# main-stm32.net
KiCad netlist of a schematic drawn in EAGLE
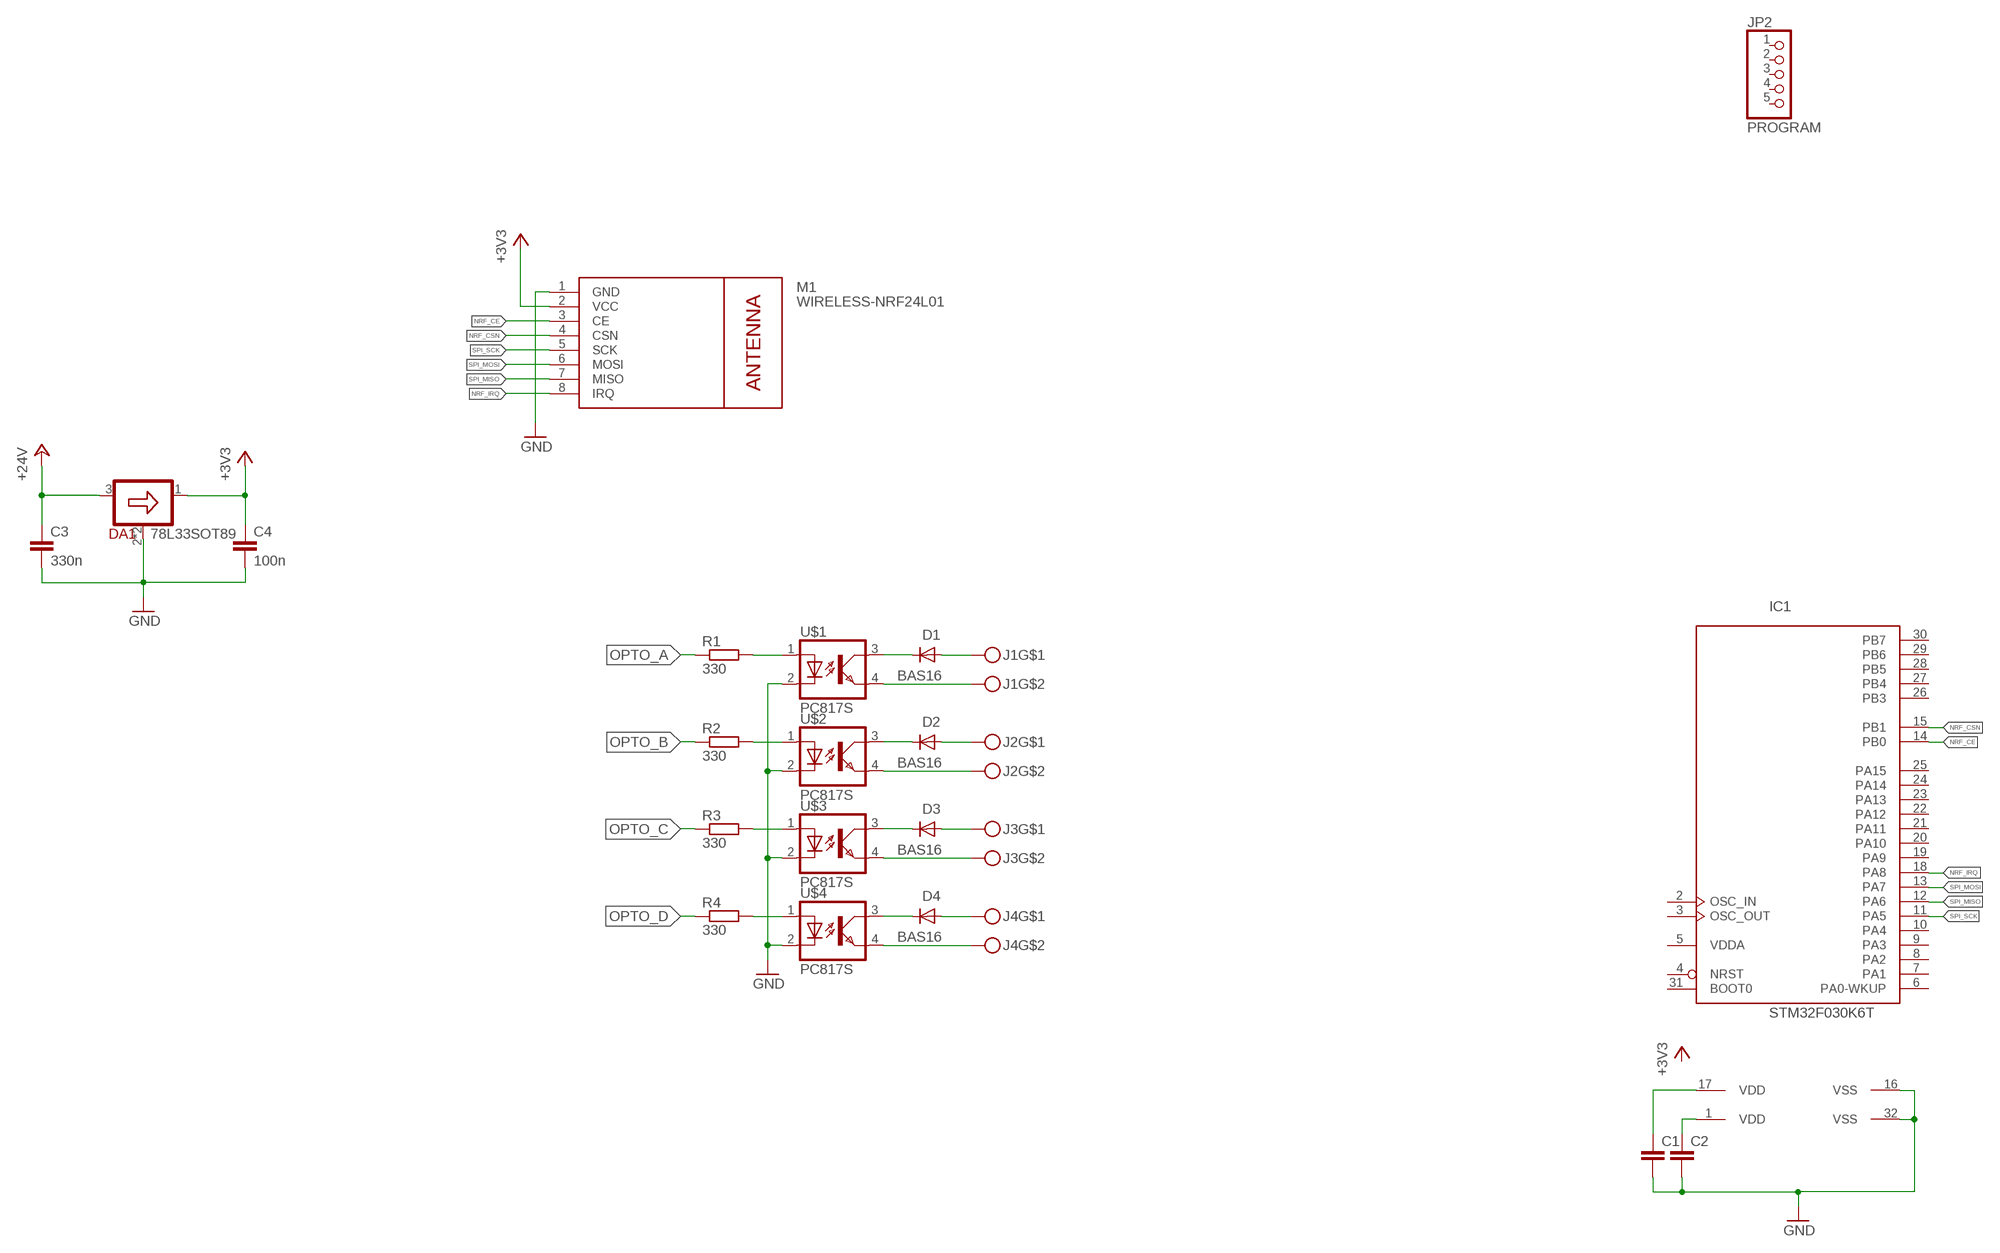
[diagram p0: schematic, sheet 1]

(export (version "E")
  (design (tool "Eeschema 10.0.6"))
  (components
    (comp (ref "C1")
      (value "C-EUC1206")
      (footprint "eagle-import:C1206")
      (libsource (lib "eagle-import") (part "C-EUC1206"))
    )
    (comp (ref "C2")
      (value "C-EUC1206")
      (footprint "eagle-import:C1206")
      (libsource (lib "eagle-import") (part "C-EUC1206"))
    )
    (comp (ref "C3")
      (value "330n")
      (footprint "eagle-import:C1206")
      (libsource (lib "eagle-import") (part "C-EUC1206"))
    )
    (comp (ref "C4")
      (value "100n")
      (footprint "eagle-import:C1206")
      (libsource (lib "eagle-import") (part "C-EUC1206"))
    )
    (comp (ref "D1")
      (value "BAS16")
      (footprint "eagle-import:SOT23")
      (libsource (lib "eagle-import") (part "BAS16"))
    )
    (comp (ref "D2")
      (value "BAS16")
      (footprint "eagle-import:SOT23")
      (libsource (lib "eagle-import") (part "BAS16"))
    )
    (comp (ref "D3")
      (value "BAS16")
      (footprint "eagle-import:SOT23")
      (libsource (lib "eagle-import") (part "BAS16"))
    )
    (comp (ref "D4")
      (value "BAS16")
      (footprint "eagle-import:SOT23")
      (libsource (lib "eagle-import") (part "BAS16"))
    )
    (comp (ref "DA1")
      (value "78L33SOT89")
      (footprint "eagle-import:SOT89")
      (libsource (lib "eagle-import") (part "78L33SOT89"))
    )
    (comp (ref "IC1")
      (value "STM32F030K6T")
      (footprint "eagle-import:LQFP32")
      (libsource (lib "eagle-import") (part "STM32F030KT6"))
    )
    (comp (ref "J1")
      (value "SCREW-TERMINAL-2PIN")
      (footprint "eagle-import:PITCH4.3-PIN2")
      (libsource (lib "eagle-import") (part "SCREW-TERMINAL-2PIN"))
    )
    (comp (ref "J2")
      (value "SCREW-TERMINAL-2PIN")
      (footprint "eagle-import:PITCH4.3-PIN2")
      (libsource (lib "eagle-import") (part "SCREW-TERMINAL-2PIN"))
    )
    (comp (ref "J3")
      (value "SCREW-TERMINAL-2PIN")
      (footprint "eagle-import:PITCH4.3-PIN2")
      (libsource (lib "eagle-import") (part "SCREW-TERMINAL-2PIN"))
    )
    (comp (ref "J4")
      (value "SCREW-TERMINAL-2PIN")
      (footprint "eagle-import:PITCH4.3-PIN2")
      (libsource (lib "eagle-import") (part "SCREW-TERMINAL-2PIN"))
    )
    (comp (ref "JP2")
      (value "PROGRAM")
      (footprint "eagle-import:1X05")
      (libsource (lib "eagle-import") (part "PINHD-1X5"))
    )
    (comp (ref "M1")
      (value "WIRELESS-NRF24L01")
      (footprint "eagle-import:WIRELESS-NRF24L01")
      (libsource (lib "eagle-import") (part "WIRELESS-NRF24L01"))
    )
    (comp (ref "R1")
      (value "330")
      (footprint "eagle-import:R1206")
      (libsource (lib "eagle-import") (part "R-EU_R1206"))
    )
    (comp (ref "R2")
      (value "330")
      (footprint "eagle-import:R1206")
      (libsource (lib "eagle-import") (part "R-EU_R1206"))
    )
    (comp (ref "R3")
      (value "330")
      (footprint "eagle-import:R1206")
      (libsource (lib "eagle-import") (part "R-EU_R1206"))
    )
    (comp (ref "R4")
      (value "330")
      (footprint "eagle-import:R1206")
      (libsource (lib "eagle-import") (part "R-EU_R1206"))
    )
    (comp (ref "U$1")
      (value "PC817S")
      (footprint "eagle-import:SMD4-7")
      (libsource (lib "eagle-import") (part "PC817S"))
    )
    (comp (ref "U$2")
      (value "PC817S")
      (footprint "eagle-import:SMD4-7")
      (libsource (lib "eagle-import") (part "PC817S"))
    )
    (comp (ref "U$3")
      (value "PC817S")
      (footprint "eagle-import:SMD4-7")
      (libsource (lib "eagle-import") (part "PC817S"))
    )
    (comp (ref "U$4")
      (value "PC817S")
      (footprint "eagle-import:SMD4-7")
      (libsource (lib "eagle-import") (part "PC817S"))
    )
  )
  (nets
    (net (code "1") (name "+3V3") (class "Default")
      (node (ref "C4") (pin "1") (pinfunction "1_1") (pintype "passive"))
      (node (ref "DA1") (pin "1") (pinfunction "OUT_1") (pintype "power_in"))
      (node (ref "M1") (pin "2") (pinfunction "VCC_2") (pintype "power_in"))
    )
    (net (code "2") (name "+24V") (class "Default")
      (node (ref "C3") (pin "1") (pinfunction "1_1") (pintype "passive"))
      (node (ref "DA1") (pin "3") (pinfunction "IN_3") (pintype "power_in"))
    )
    (net (code "3") (name "/VDDA") (class "Default")
      (node (ref "IC1") (pin "5") (pinfunction "VDDA_5") (pintype "power_in"))
    )
    (net (code "4") (name "GND") (class "Default")
      (node (ref "C1") (pin "2") (pinfunction "2_2") (pintype "passive"))
      (node (ref "C2") (pin "2") (pinfunction "2_2") (pintype "passive"))
      (node (ref "C3") (pin "2") (pinfunction "2_2") (pintype "passive"))
      (node (ref "C4") (pin "2") (pinfunction "2_2") (pintype "passive"))
      (node (ref "DA1") (pin "2") (pinfunction "GND_2") (pintype "power_in"))
      (node (ref "DA1") (pin "2@1") (pinfunction "GND_2@1") (pintype "power_in"))
      (node (ref "IC1") (pin "16") (pinfunction "VSS_16") (pintype "power_in"))
      (node (ref "IC1") (pin "32") (pinfunction "VSS_32") (pintype "power_in"))
      (node (ref "M1") (pin "1") (pinfunction "GND_1") (pintype "power_in"))
      (node (ref "U$1") (pin "2") (pinfunction "C_2") (pintype "passive"))
      (node (ref "U$2") (pin "2") (pinfunction "C_2") (pintype "passive"))
      (node (ref "U$3") (pin "2") (pinfunction "C_2") (pintype "passive"))
      (node (ref "U$4") (pin "2") (pinfunction "C_2") (pintype "passive"))
    )
    (net (code "5") (name "NRF_CE") (class "Default")
      (node (ref "IC1") (pin "14") (pinfunction "PB0_14") (pintype "bidirectional"))
      (node (ref "M1") (pin "3") (pinfunction "CE_3") (pintype "bidirectional"))
    )
    (net (code "6") (name "NRF_CSN") (class "Default")
      (node (ref "IC1") (pin "15") (pinfunction "PB1_15") (pintype "bidirectional"))
      (node (ref "M1") (pin "4") (pinfunction "CSN_4") (pintype "bidirectional"))
    )
    (net (code "7") (name "NRF_IRQ") (class "Default")
      (node (ref "IC1") (pin "18") (pinfunction "PA8_18") (pintype "bidirectional"))
      (node (ref "M1") (pin "8") (pinfunction "IRQ_8") (pintype "bidirectional"))
    )
    (net (code "8") (name "Net-(C1-Pad1)") (class "Default")
      (node (ref "C1") (pin "1") (pinfunction "1_1") (pintype "passive"))
      (node (ref "IC1") (pin "17") (pinfunction "VDD_17") (pintype "power_in"))
    )
    (net (code "9") (name "Net-(C2-Pad1)") (class "Default")
      (node (ref "C2") (pin "1") (pinfunction "1_1") (pintype "passive"))
      (node (ref "IC1") (pin "1") (pinfunction "VDD_1") (pintype "power_in"))
    )
    (net (code "10") (name "Net-(D1-A)") (class "Default")
      (node (ref "D1") (pin "1") (pinfunction "A_1") (pintype "passive"))
      (node (ref "J1") (pin "1") (pinfunction "KL_1") (pintype "passive"))
    )
    (net (code "11") (name "Net-(D1-K)") (class "Default")
      (node (ref "D1") (pin "3") (pinfunction "K_3") (pintype "passive"))
      (node (ref "U$1") (pin "3") (pinfunction "COL_3") (pintype "passive"))
    )
    (net (code "12") (name "Net-(D2-A)") (class "Default")
      (node (ref "D2") (pin "1") (pinfunction "A_1") (pintype "passive"))
      (node (ref "J2") (pin "1") (pinfunction "KL_1") (pintype "passive"))
    )
    (net (code "13") (name "Net-(D2-K)") (class "Default")
      (node (ref "D2") (pin "3") (pinfunction "K_3") (pintype "passive"))
      (node (ref "U$2") (pin "3") (pinfunction "COL_3") (pintype "passive"))
    )
    (net (code "14") (name "Net-(D3-A)") (class "Default")
      (node (ref "D3") (pin "1") (pinfunction "A_1") (pintype "passive"))
      (node (ref "J3") (pin "1") (pinfunction "KL_1") (pintype "passive"))
    )
    (net (code "15") (name "Net-(D3-K)") (class "Default")
      (node (ref "D3") (pin "3") (pinfunction "K_3") (pintype "passive"))
      (node (ref "U$3") (pin "3") (pinfunction "COL_3") (pintype "passive"))
    )
    (net (code "16") (name "Net-(D4-A)") (class "Default")
      (node (ref "D4") (pin "1") (pinfunction "A_1") (pintype "passive"))
      (node (ref "J4") (pin "1") (pinfunction "KL_1") (pintype "passive"))
    )
    (net (code "17") (name "Net-(D4-K)") (class "Default")
      (node (ref "D4") (pin "3") (pinfunction "K_3") (pintype "passive"))
      (node (ref "U$4") (pin "3") (pinfunction "COL_3") (pintype "passive"))
    )
    (net (code "18") (name "Net-(J1B-KL)") (class "Default")
      (node (ref "J1") (pin "2") (pinfunction "KL_2") (pintype "passive"))
      (node (ref "U$1") (pin "4") (pinfunction "EMIT_4") (pintype "passive"))
    )
    (net (code "19") (name "Net-(J2B-KL)") (class "Default")
      (node (ref "J2") (pin "2") (pinfunction "KL_2") (pintype "passive"))
      (node (ref "U$2") (pin "4") (pinfunction "EMIT_4") (pintype "passive"))
    )
    (net (code "20") (name "Net-(J3B-KL)") (class "Default")
      (node (ref "J3") (pin "2") (pinfunction "KL_2") (pintype "passive"))
      (node (ref "U$3") (pin "4") (pinfunction "EMIT_4") (pintype "passive"))
    )
    (net (code "21") (name "Net-(J4B-KL)") (class "Default")
      (node (ref "J4") (pin "2") (pinfunction "KL_2") (pintype "passive"))
      (node (ref "U$4") (pin "4") (pinfunction "EMIT_4") (pintype "passive"))
    )
    (net (code "22") (name "Net-(U$1-A)") (class "Default")
      (node (ref "R1") (pin "2") (pinfunction "2_2") (pintype "passive"))
      (node (ref "U$1") (pin "1") (pinfunction "A_1") (pintype "passive"))
    )
    (net (code "23") (name "Net-(U$2-A)") (class "Default")
      (node (ref "R2") (pin "2") (pinfunction "2_2") (pintype "passive"))
      (node (ref "U$2") (pin "1") (pinfunction "A_1") (pintype "passive"))
    )
    (net (code "24") (name "Net-(U$3-A)") (class "Default")
      (node (ref "R3") (pin "2") (pinfunction "2_2") (pintype "passive"))
      (node (ref "U$3") (pin "1") (pinfunction "A_1") (pintype "passive"))
    )
    (net (code "25") (name "Net-(U$4-A)") (class "Default")
      (node (ref "R4") (pin "2") (pinfunction "2_2") (pintype "passive"))
      (node (ref "U$4") (pin "1") (pinfunction "A_1") (pintype "passive"))
    )
    (net (code "26") (name "OPTO_A") (class "Default")
      (node (ref "R1") (pin "1") (pinfunction "1_1") (pintype "passive"))
    )
    (net (code "27") (name "OPTO_B") (class "Default")
      (node (ref "R2") (pin "1") (pinfunction "1_1") (pintype "passive"))
    )
    (net (code "28") (name "OPTO_C") (class "Default")
      (node (ref "R3") (pin "1") (pinfunction "1_1") (pintype "passive"))
    )
    (net (code "29") (name "OPTO_D") (class "Default")
      (node (ref "R4") (pin "1") (pinfunction "1_1") (pintype "passive"))
    )
    (net (code "30") (name "SPI_MISO") (class "Default")
      (node (ref "IC1") (pin "12") (pinfunction "PA6_12") (pintype "bidirectional"))
      (node (ref "M1") (pin "7") (pinfunction "MISO_7") (pintype "bidirectional"))
    )
    (net (code "31") (name "SPI_MOSI") (class "Default")
      (node (ref "IC1") (pin "13") (pinfunction "PA7_13") (pintype "bidirectional"))
      (node (ref "M1") (pin "6") (pinfunction "MOSI_6") (pintype "bidirectional"))
    )
    (net (code "32") (name "SPI_SCK") (class "Default")
      (node (ref "IC1") (pin "11") (pinfunction "PA5_11") (pintype "bidirectional"))
      (node (ref "M1") (pin "5") (pinfunction "SCK_5") (pintype "bidirectional"))
    )
    (net (code "33") (name "unconnected-(IC1A-BOOT0-Pad31)") (class "Default")
      (node (ref "IC1") (pin "31") (pinfunction "BOOT0_31") (pintype "input"))
    )
    (net (code "34") (name "unconnected-(IC1A-NRST-Pad4)") (class "Default")
      (node (ref "IC1") (pin "4") (pinfunction "NRST_4") (pintype "bidirectional"))
    )
    (net (code "35") (name "unconnected-(IC1A-OSC_IN-Pad2)") (class "Default")
      (node (ref "IC1") (pin "2") (pinfunction "OSC_IN_2") (pintype "bidirectional"))
    )
    (net (code "36") (name "unconnected-(IC1A-OSC_OUT-Pad3)") (class "Default")
      (node (ref "IC1") (pin "3") (pinfunction "OSC_OUT_3") (pintype "bidirectional"))
    )
    (net (code "37") (name "unconnected-(IC1A-PA0-WKUP-Pad6)") (class "Default")
      (node (ref "IC1") (pin "6") (pinfunction "PA0-WKUP_6") (pintype "bidirectional"))
    )
    (net (code "38") (name "unconnected-(IC1A-PA1-Pad7)") (class "Default")
      (node (ref "IC1") (pin "7") (pinfunction "PA1_7") (pintype "bidirectional"))
    )
    (net (code "39") (name "unconnected-(IC1A-PA2-Pad8)") (class "Default")
      (node (ref "IC1") (pin "8") (pinfunction "PA2_8") (pintype "bidirectional"))
    )
    (net (code "40") (name "unconnected-(IC1A-PA3-Pad9)") (class "Default")
      (node (ref "IC1") (pin "9") (pinfunction "PA3_9") (pintype "bidirectional"))
    )
    (net (code "41") (name "unconnected-(IC1A-PA4-Pad10)") (class "Default")
      (node (ref "IC1") (pin "10") (pinfunction "PA4_10") (pintype "bidirectional"))
    )
    (net (code "42") (name "unconnected-(IC1A-PA9-Pad19)") (class "Default")
      (node (ref "IC1") (pin "19") (pinfunction "PA9_19") (pintype "bidirectional"))
    )
    (net (code "43") (name "unconnected-(IC1A-PA10-Pad20)") (class "Default")
      (node (ref "IC1") (pin "20") (pinfunction "PA10_20") (pintype "bidirectional"))
    )
    (net (code "44") (name "unconnected-(IC1A-PA11-Pad21)") (class "Default")
      (node (ref "IC1") (pin "21") (pinfunction "PA11_21") (pintype "bidirectional"))
    )
    (net (code "45") (name "unconnected-(IC1A-PA12-Pad22)") (class "Default")
      (node (ref "IC1") (pin "22") (pinfunction "PA12_22") (pintype "bidirectional"))
    )
    (net (code "46") (name "unconnected-(IC1A-PA13-Pad23)") (class "Default")
      (node (ref "IC1") (pin "23") (pinfunction "PA13_23") (pintype "bidirectional"))
    )
    (net (code "47") (name "unconnected-(IC1A-PA14-Pad24)") (class "Default")
      (node (ref "IC1") (pin "24") (pinfunction "PA14_24") (pintype "bidirectional"))
    )
    (net (code "48") (name "unconnected-(IC1A-PA15-Pad25)") (class "Default")
      (node (ref "IC1") (pin "25") (pinfunction "PA15_25") (pintype "bidirectional"))
    )
    (net (code "49") (name "unconnected-(IC1A-PB3-Pad26)") (class "Default")
      (node (ref "IC1") (pin "26") (pinfunction "PB3_26") (pintype "bidirectional"))
    )
    (net (code "50") (name "unconnected-(IC1A-PB4-Pad27)") (class "Default")
      (node (ref "IC1") (pin "27") (pinfunction "PB4_27") (pintype "bidirectional"))
    )
    (net (code "51") (name "unconnected-(IC1A-PB5-Pad28)") (class "Default")
      (node (ref "IC1") (pin "28") (pinfunction "PB5_28") (pintype "bidirectional"))
    )
    (net (code "52") (name "unconnected-(IC1A-PB6-Pad29)") (class "Default")
      (node (ref "IC1") (pin "29") (pinfunction "PB6_29") (pintype "bidirectional"))
    )
    (net (code "53") (name "unconnected-(IC1A-PB7-Pad30)") (class "Default")
      (node (ref "IC1") (pin "30") (pinfunction "PB7_30") (pintype "bidirectional"))
    )
    (net (code "54") (name "unconnected-(JP2-Pad1)") (class "Default")
      (node (ref "JP2") (pin "1") (pinfunction "1_1") (pintype "passive"))
    )
    (net (code "55") (name "unconnected-(JP2-Pad2)") (class "Default")
      (node (ref "JP2") (pin "2") (pinfunction "2_2") (pintype "passive"))
    )
    (net (code "56") (name "unconnected-(JP2-Pad3)") (class "Default")
      (node (ref "JP2") (pin "3") (pinfunction "3_3") (pintype "passive"))
    )
    (net (code "57") (name "unconnected-(JP2-Pad4)") (class "Default")
      (node (ref "JP2") (pin "4") (pinfunction "4_4") (pintype "passive"))
    )
    (net (code "58") (name "unconnected-(JP2-Pad5)") (class "Default")
      (node (ref "JP2") (pin "5") (pinfunction "5_5") (pintype "passive"))
    )
  )
)
